# TelTail_Breakout_3v0.net
KiCad netlist of a schematic drawn in EAGLE
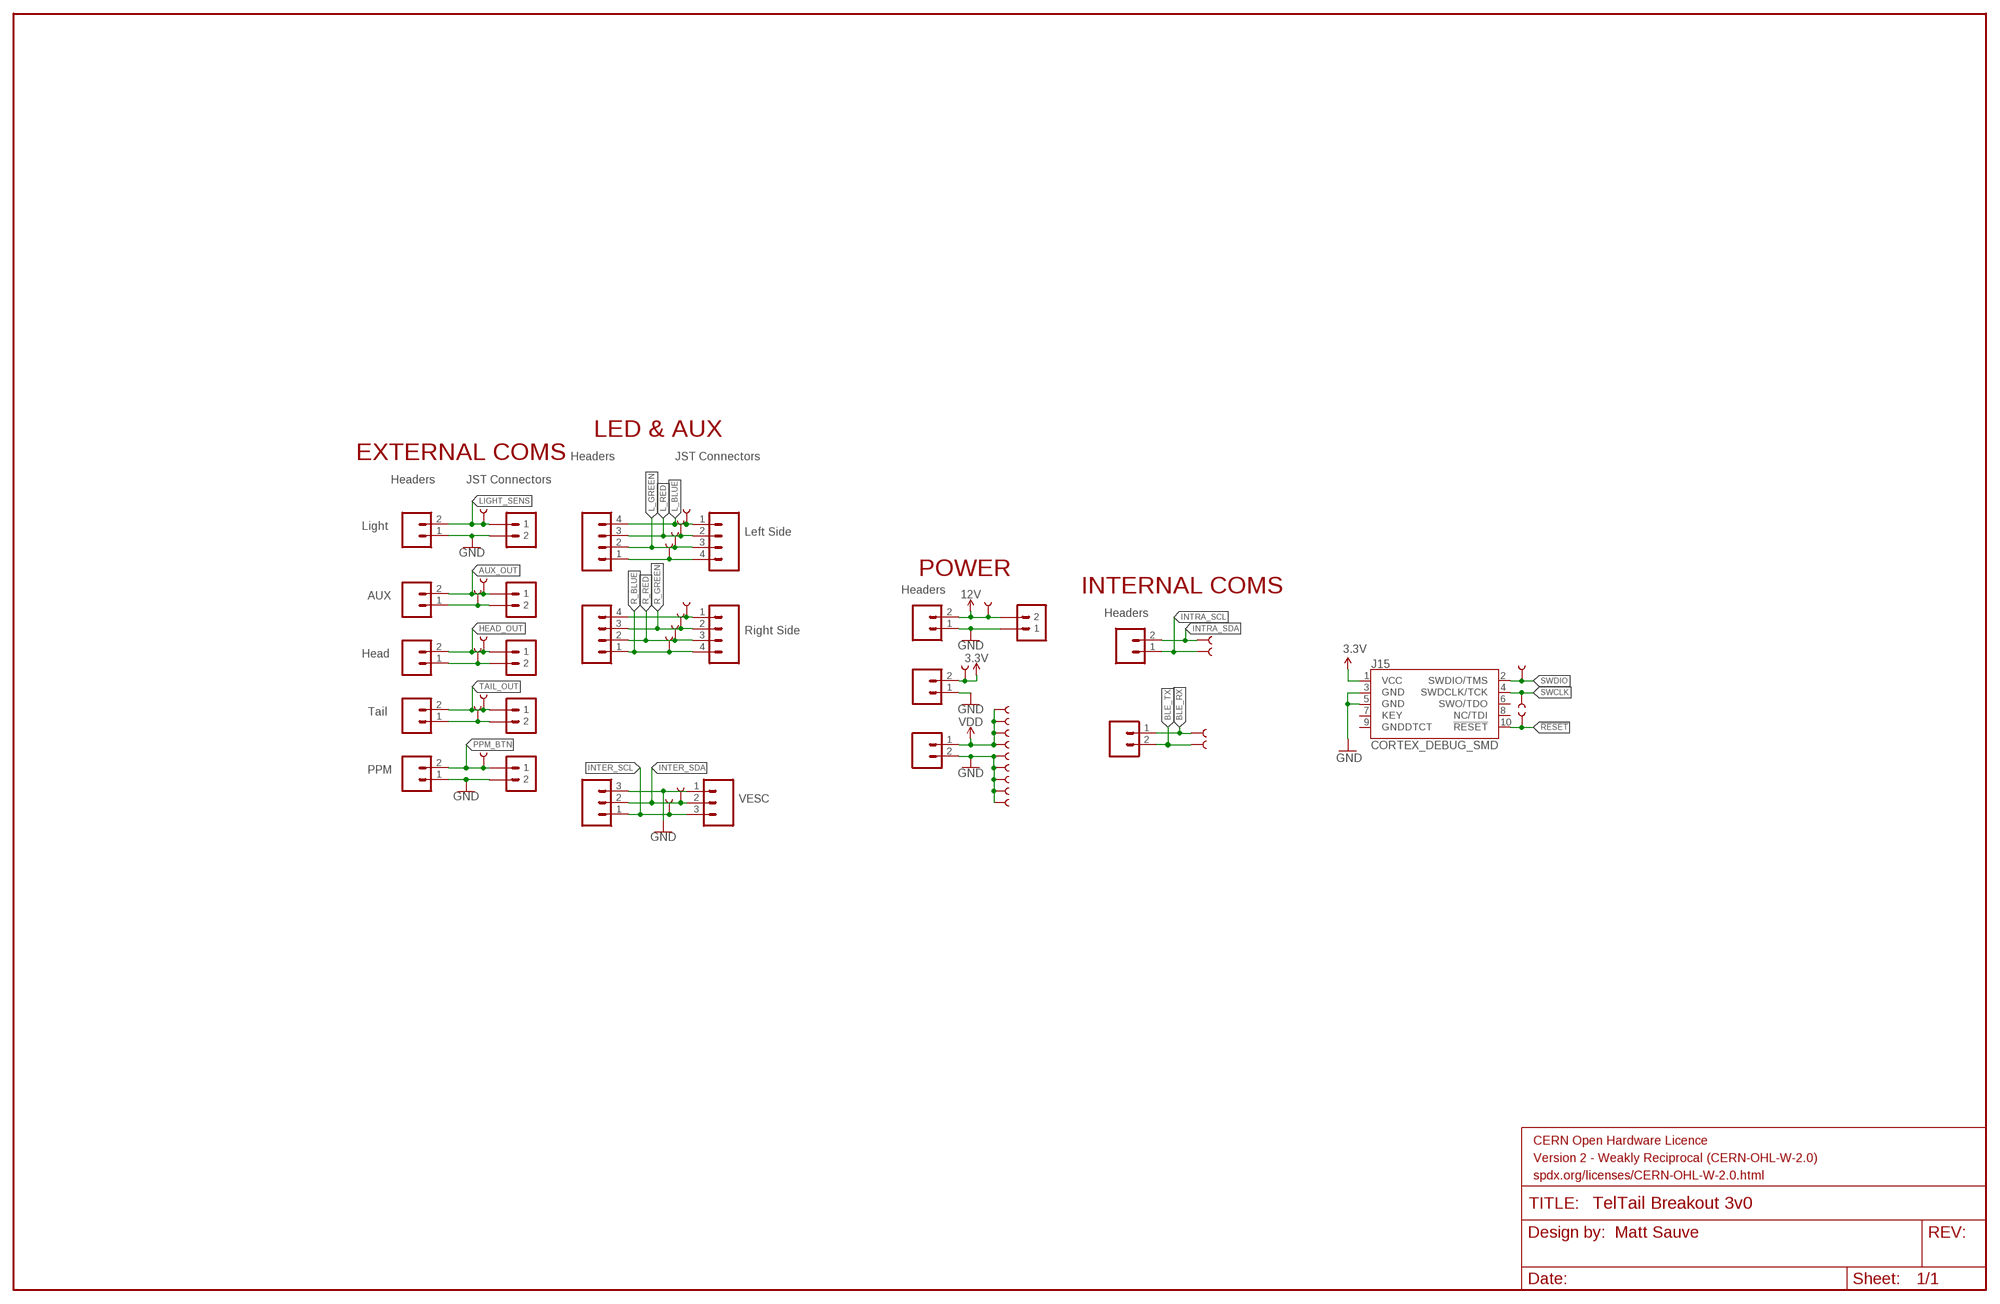
[diagram p0: schematic, sheet 1]

(export (version "E")
  (design (tool "Eeschema 10.0.6"))
  (components
    (comp (ref "FRAME1")
      (value "FRAME-LEDGER_CERN_WEAK")
      (footprint "eagle-import:CERN_WEAK")
      (libsource (lib "eagle-import") (part "FRAME-LEDGER_CERN_WEAK"))
    )
    (comp (ref "J1")
      (value "CONN_02")
      (footprint "eagle-import:1X02")
      (libsource (lib "eagle-import") (part "CONN_02"))
    )
    (comp (ref "J2")
      (value "CONN_02")
      (footprint "eagle-import:1X02")
      (libsource (lib "eagle-import") (part "CONN_02"))
    )
    (comp (ref "J3")
      (value "CONN_02")
      (footprint "eagle-import:1X02")
      (libsource (lib "eagle-import") (part "CONN_02"))
    )
    (comp (ref "J4")
      (value "CONN_02")
      (footprint "eagle-import:1X02")
      (libsource (lib "eagle-import") (part "CONN_02"))
    )
    (comp (ref "J5")
      (value "CONN_02")
      (footprint "eagle-import:1X02")
      (libsource (lib "eagle-import") (part "CONN_02"))
    )
    (comp (ref "J6")
      (value "CONN_02")
      (footprint "eagle-import:1X02")
      (libsource (lib "eagle-import") (part "CONN_02"))
    )
    (comp (ref "J7")
      (value "CONN_03")
      (footprint "eagle-import:1X03")
      (libsource (lib "eagle-import") (part "CONN_03"))
    )
    (comp (ref "J9")
      (value "CONN_04")
      (footprint "eagle-import:1X04")
      (libsource (lib "eagle-import") (part "CONN_04"))
    )
    (comp (ref "J10")
      (value "CONN_04")
      (footprint "eagle-import:1X04")
      (libsource (lib "eagle-import") (part "CONN_04"))
    )
    (comp (ref "J11")
      (value "CONN_02")
      (footprint "eagle-import:1X02")
      (libsource (lib "eagle-import") (part "CONN_02"))
    )
    (comp (ref "J12")
      (value "CONN_02")
      (footprint "eagle-import:1X02")
      (libsource (lib "eagle-import") (part "CONN_02"))
    )
    (comp (ref "J13")
      (value "CONN_02")
      (footprint "eagle-import:1X02")
      (libsource (lib "eagle-import") (part "CONN_02"))
    )
    (comp (ref "J14")
      (value "CONN_02")
      (footprint "eagle-import:1X02")
      (libsource (lib "eagle-import") (part "CONN_02"))
    )
    (comp (ref "J15")
      (value "CORTEX_DEBUG_SMD")
      (footprint "eagle-import:SAMTECH_FTSH-105-01")
      (libsource (lib "eagle-import") (part "CORTEX_DEBUG_SMD"))
    )
    (comp (ref "U$1")
      (value "JST_PH_2POS")
      (footprint "eagle-import:JST_PH_2POS")
      (libsource (lib "eagle-import") (part "JST_PH_2POS"))
    )
    (comp (ref "U$2")
      (value "JST_PH_2POS")
      (footprint "eagle-import:JST_PH_2POS")
      (libsource (lib "eagle-import") (part "JST_PH_2POS"))
    )
    (comp (ref "U$3")
      (value "JST_PH_2POS")
      (footprint "eagle-import:JST_PH_2POS")
      (libsource (lib "eagle-import") (part "JST_PH_2POS"))
    )
    (comp (ref "U$4")
      (value "JST_PH_2POS")
      (footprint "eagle-import:JST_PH_2POS")
      (libsource (lib "eagle-import") (part "JST_PH_2POS"))
    )
    (comp (ref "U$5")
      (value "JST_PH_2POS")
      (footprint "eagle-import:JST_PH_2POS")
      (libsource (lib "eagle-import") (part "JST_PH_2POS"))
    )
    (comp (ref "U$6")
      (value "POGO_PIN_90173-AS")
      (footprint "eagle-import:POGO_PIN_90173-AS")
      (libsource (lib "eagle-import") (part "POGO_PIN_90173-AS"))
    )
    (comp (ref "U$8")
      (value "JST_PH_4POS")
      (footprint "eagle-import:JST_PH_4POS")
      (libsource (lib "eagle-import") (part "JST_PH_4POS"))
    )
    (comp (ref "U$9")
      (value "JST_PH_3POS")
      (footprint "eagle-import:JST_PH_3POS")
      (libsource (lib "eagle-import") (part "JST_PH_3POS"))
    )
    (comp (ref "U$10")
      (value "JST_PH_4POS")
      (footprint "eagle-import:JST_PH_4POS")
      (libsource (lib "eagle-import") (part "JST_PH_4POS"))
    )
    (comp (ref "U$11")
      (value "POGO_PIN_90173-AS")
      (footprint "eagle-import:POGO_PIN_90173-AS")
      (libsource (lib "eagle-import") (part "POGO_PIN_90173-AS"))
    )
    (comp (ref "U$12")
      (value "POGO_PIN_90173-AS")
      (footprint "eagle-import:POGO_PIN_90173-AS")
      (libsource (lib "eagle-import") (part "POGO_PIN_90173-AS"))
    )
    (comp (ref "U$13")
      (value "POGO_PIN_90173-AS")
      (footprint "eagle-import:POGO_PIN_90173-AS")
      (libsource (lib "eagle-import") (part "POGO_PIN_90173-AS"))
    )
    (comp (ref "U$14")
      (value "POGO_PIN_90173-AS")
      (footprint "eagle-import:POGO_PIN_90173-AS")
      (libsource (lib "eagle-import") (part "POGO_PIN_90173-AS"))
    )
    (comp (ref "U$15")
      (value "POGO_PIN_90173-AS")
      (footprint "eagle-import:POGO_PIN_90173-AS")
      (libsource (lib "eagle-import") (part "POGO_PIN_90173-AS"))
    )
    (comp (ref "U$16")
      (value "POGO_PIN_90173-AS")
      (footprint "eagle-import:POGO_PIN_90173-AS")
      (libsource (lib "eagle-import") (part "POGO_PIN_90173-AS"))
    )
    (comp (ref "U$17")
      (value "POGO_PIN_90173-AS")
      (footprint "eagle-import:POGO_PIN_90173-AS")
      (libsource (lib "eagle-import") (part "POGO_PIN_90173-AS"))
    )
    (comp (ref "U$18")
      (value "POGO_PIN_90173-AS")
      (footprint "eagle-import:POGO_PIN_90173-AS")
      (libsource (lib "eagle-import") (part "POGO_PIN_90173-AS"))
    )
    (comp (ref "U$19")
      (value "POGO_PIN_90173-AS")
      (footprint "eagle-import:POGO_PIN_90173-AS")
      (libsource (lib "eagle-import") (part "POGO_PIN_90173-AS"))
    )
    (comp (ref "U$20")
      (value "POGO_PIN_90173-AS")
      (footprint "eagle-import:POGO_PIN_90173-AS")
      (libsource (lib "eagle-import") (part "POGO_PIN_90173-AS"))
    )
    (comp (ref "U$21")
      (value "POGO_PIN_90173-AS")
      (footprint "eagle-import:POGO_PIN_90173-AS")
      (libsource (lib "eagle-import") (part "POGO_PIN_90173-AS"))
    )
    (comp (ref "U$22")
      (value "POGO_PIN_90173-AS")
      (footprint "eagle-import:POGO_PIN_90173-AS")
      (libsource (lib "eagle-import") (part "POGO_PIN_90173-AS"))
    )
    (comp (ref "U$23")
      (value "POGO_PIN_90173-AS")
      (footprint "eagle-import:POGO_PIN_90173-AS")
      (libsource (lib "eagle-import") (part "POGO_PIN_90173-AS"))
    )
    (comp (ref "U$24")
      (value "POGO_PIN_90173-AS")
      (footprint "eagle-import:POGO_PIN_90173-AS")
      (libsource (lib "eagle-import") (part "POGO_PIN_90173-AS"))
    )
    (comp (ref "U$25")
      (value "POGO_PIN_90173-AS")
      (footprint "eagle-import:POGO_PIN_90173-AS")
      (libsource (lib "eagle-import") (part "POGO_PIN_90173-AS"))
    )
    (comp (ref "U$26")
      (value "POGO_PIN_90173-AS")
      (footprint "eagle-import:POGO_PIN_90173-AS")
      (libsource (lib "eagle-import") (part "POGO_PIN_90173-AS"))
    )
    (comp (ref "U$27")
      (value "POGO_PIN_90173-AS")
      (footprint "eagle-import:POGO_PIN_90173-AS")
      (libsource (lib "eagle-import") (part "POGO_PIN_90173-AS"))
    )
    (comp (ref "U$28")
      (value "POGO_PIN_90173-AS")
      (footprint "eagle-import:POGO_PIN_90173-AS")
      (libsource (lib "eagle-import") (part "POGO_PIN_90173-AS"))
    )
    (comp (ref "U$29")
      (value "POGO_PIN_90173-AS")
      (footprint "eagle-import:POGO_PIN_90173-AS")
      (libsource (lib "eagle-import") (part "POGO_PIN_90173-AS"))
    )
    (comp (ref "U$30")
      (value "POGO_PIN_90173-AS")
      (footprint "eagle-import:POGO_PIN_90173-AS")
      (libsource (lib "eagle-import") (part "POGO_PIN_90173-AS"))
    )
    (comp (ref "U$31")
      (value "POGO_PIN_90173-AS")
      (footprint "eagle-import:POGO_PIN_90173-AS")
      (libsource (lib "eagle-import") (part "POGO_PIN_90173-AS"))
    )
    (comp (ref "U$32")
      (value "POGO_PIN_90173-AS")
      (footprint "eagle-import:POGO_PIN_90173-AS")
      (libsource (lib "eagle-import") (part "POGO_PIN_90173-AS"))
    )
    (comp (ref "U$33")
      (value "POGO_PIN_90173-AS")
      (footprint "eagle-import:POGO_PIN_90173-AS")
      (libsource (lib "eagle-import") (part "POGO_PIN_90173-AS"))
    )
    (comp (ref "U$34")
      (value "POGO_PIN_90173-AS")
      (footprint "eagle-import:POGO_PIN_90173-AS")
      (libsource (lib "eagle-import") (part "POGO_PIN_90173-AS"))
    )
    (comp (ref "U$35")
      (value "POGO_PIN_90173-AS")
      (footprint "eagle-import:POGO_PIN_90173-AS")
      (libsource (lib "eagle-import") (part "POGO_PIN_90173-AS"))
    )
    (comp (ref "U$36")
      (value "POGO_PIN_90173-AS")
      (footprint "eagle-import:POGO_PIN_90173-AS")
      (libsource (lib "eagle-import") (part "POGO_PIN_90173-AS"))
    )
    (comp (ref "U$37")
      (value "POGO_PIN_90173-AS")
      (footprint "eagle-import:POGO_PIN_90173-AS")
      (libsource (lib "eagle-import") (part "POGO_PIN_90173-AS"))
    )
    (comp (ref "U$38")
      (value "POGO_PIN_90173-AS")
      (footprint "eagle-import:POGO_PIN_90173-AS")
      (libsource (lib "eagle-import") (part "POGO_PIN_90173-AS"))
    )
    (comp (ref "U$39")
      (value "POGO_PIN_90173-AS")
      (footprint "eagle-import:POGO_PIN_90173-AS")
      (libsource (lib "eagle-import") (part "POGO_PIN_90173-AS"))
    )
    (comp (ref "U$40")
      (value "POGO_PIN_90173-AS")
      (footprint "eagle-import:POGO_PIN_90173-AS")
      (libsource (lib "eagle-import") (part "POGO_PIN_90173-AS"))
    )
    (comp (ref "U$42")
      (value "POGO_PIN_90173-AS")
      (footprint "eagle-import:POGO_PIN_90173-AS")
      (libsource (lib "eagle-import") (part "POGO_PIN_90173-AS"))
    )
    (comp (ref "U$43")
      (value "POGO_PIN_90173-AS")
      (footprint "eagle-import:POGO_PIN_90173-AS")
      (libsource (lib "eagle-import") (part "POGO_PIN_90173-AS"))
    )
    (comp (ref "U$44")
      (value "POGO_PIN_90173-AS")
      (footprint "eagle-import:POGO_PIN_90173-AS")
      (libsource (lib "eagle-import") (part "POGO_PIN_90173-AS"))
    )
    (comp (ref "U$45")
      (value "JST_PH_2POS")
      (footprint "eagle-import:JST_PH_2POS")
      (libsource (lib "eagle-import") (part "JST_PH_2POS"))
    )
    (comp (ref "U$46")
      (value "POGO_PIN_90173-AS")
      (footprint "eagle-import:POGO_PIN_90173-AS")
      (libsource (lib "eagle-import") (part "POGO_PIN_90173-AS"))
    )
    (comp (ref "U$48")
      (value "POGO_PIN_90173-AS")
      (footprint "eagle-import:POGO_PIN_90173-AS")
      (libsource (lib "eagle-import") (part "POGO_PIN_90173-AS"))
    )
  )
  (nets
    (net (code "1") (name "/~{RESET}") (class "Default")
      (node (ref "J15") (pin "10") (pinfunction "~{RESET}_10") (pintype "bidirectional"))
      (node (ref "U$36") (pin "P$1") (pinfunction "1_P$1") (pintype "bidirectional"))
    )
    (net (code "2") (name "3.3V") (class "Default")
      (node (ref "J12") (pin "2") (pinfunction "2_2") (pintype "passive"))
      (node (ref "J15") (pin "1") (pinfunction "VCC_1") (pintype "bidirectional"))
      (node (ref "U$20") (pin "P$1") (pinfunction "1_P$1") (pintype "bidirectional"))
    )
    (net (code "3") (name "12V") (class "Default")
      (node (ref "J11") (pin "2") (pinfunction "2_2") (pintype "passive"))
      (node (ref "U$38") (pin "P$1") (pinfunction "1_P$1") (pintype "bidirectional"))
      (node (ref "U$45") (pin "2") (pinfunction "2_2") (pintype "passive"))
    )
    (net (code "4") (name "AUX_OUT") (class "Default")
      (node (ref "J2") (pin "2") (pinfunction "2_2") (pintype "passive"))
      (node (ref "U$31") (pin "P$1") (pinfunction "1_P$1") (pintype "bidirectional"))
      (node (ref "U$4") (pin "1") (pinfunction "1_1") (pintype "passive"))
    )
    (net (code "5") (name "BLE_RX") (class "Default")
      (node (ref "J14") (pin "1") (pinfunction "1_1") (pintype "passive"))
      (node (ref "U$46") (pin "P$1") (pinfunction "1_P$1") (pintype "bidirectional"))
    )
    (net (code "6") (name "BLE_TX") (class "Default")
      (node (ref "J14") (pin "2") (pinfunction "2_2") (pintype "passive"))
      (node (ref "U$48") (pin "P$1") (pinfunction "1_P$1") (pintype "bidirectional"))
    )
    (net (code "7") (name "GND") (class "Default")
      (node (ref "J1") (pin "1") (pinfunction "1_1") (pintype "passive"))
      (node (ref "J11") (pin "1") (pinfunction "1_1") (pintype "passive"))
      (node (ref "J12") (pin "1") (pinfunction "1_1") (pintype "passive"))
      (node (ref "J15") (pin "3") (pinfunction "GND_3") (pintype "bidirectional"))
      (node (ref "J15") (pin "5") (pinfunction "GND_5") (pintype "bidirectional"))
      (node (ref "J5") (pin "1") (pinfunction "1_1") (pintype "passive"))
      (node (ref "J6") (pin "2") (pinfunction "2_2") (pintype "passive"))
      (node (ref "J7") (pin "3") (pinfunction "3_3") (pintype "passive"))
      (node (ref "U$1") (pin "2") (pinfunction "2_2") (pintype "passive"))
      (node (ref "U$24") (pin "P$1") (pinfunction "1_P$1") (pintype "bidirectional"))
      (node (ref "U$28") (pin "P$1") (pinfunction "1_P$1") (pintype "bidirectional"))
      (node (ref "U$30") (pin "P$1") (pinfunction "1_P$1") (pintype "bidirectional"))
      (node (ref "U$40") (pin "P$1") (pinfunction "1_P$1") (pintype "bidirectional"))
      (node (ref "U$45") (pin "1") (pinfunction "1_1") (pintype "passive"))
      (node (ref "U$5") (pin "2") (pinfunction "2_2") (pintype "passive"))
      (node (ref "U$6") (pin "P$1") (pinfunction "1_P$1") (pintype "bidirectional"))
      (node (ref "U$9") (pin "1") (pinfunction "2_1") (pintype "passive"))
    )
    (net (code "8") (name "HEAD_OUT") (class "Default")
      (node (ref "J3") (pin "2") (pinfunction "2_2") (pintype "passive"))
      (node (ref "U$29") (pin "P$1") (pinfunction "1_P$1") (pintype "bidirectional"))
      (node (ref "U$3") (pin "1") (pinfunction "1_1") (pintype "passive"))
    )
    (net (code "9") (name "INTER_SCL") (class "Default")
      (node (ref "J7") (pin "1") (pinfunction "1_1") (pintype "passive"))
      (node (ref "U$19") (pin "P$1") (pinfunction "1_P$1") (pintype "bidirectional"))
      (node (ref "U$9") (pin "3") (pinfunction "4_3") (pintype "passive"))
    )
    (net (code "10") (name "INTER_SDA") (class "Default")
      (node (ref "J7") (pin "2") (pinfunction "2_2") (pintype "passive"))
      (node (ref "U$21") (pin "P$1") (pinfunction "1_P$1") (pintype "bidirectional"))
      (node (ref "U$9") (pin "2") (pinfunction "3_2") (pintype "passive"))
    )
    (net (code "11") (name "INTRA_SCL") (class "Default")
      (node (ref "J13") (pin "1") (pinfunction "1_1") (pintype "passive"))
      (node (ref "U$44") (pin "P$1") (pinfunction "1_P$1") (pintype "bidirectional"))
    )
    (net (code "12") (name "INTRA_SDA") (class "Default")
      (node (ref "J13") (pin "2") (pinfunction "2_2") (pintype "passive"))
      (node (ref "U$43") (pin "P$1") (pinfunction "1_P$1") (pintype "bidirectional"))
    )
    (net (code "13") (name "LIGHT_SENS") (class "Default")
      (node (ref "J1") (pin "2") (pinfunction "2_2") (pintype "passive"))
      (node (ref "U$33") (pin "P$1") (pinfunction "1_P$1") (pintype "bidirectional"))
      (node (ref "U$5") (pin "1") (pinfunction "1_1") (pintype "passive"))
    )
    (net (code "14") (name "L_BLUE") (class "Default")
      (node (ref "J10") (pin "4") (pinfunction "4_4") (pintype "passive"))
      (node (ref "U$10") (pin "1") (pinfunction "1_1") (pintype "passive"))
      (node (ref "U$11") (pin "P$1") (pinfunction "1_P$1") (pintype "bidirectional"))
    )
    (net (code "15") (name "L_GREEN") (class "Default")
      (node (ref "J10") (pin "2") (pinfunction "2_2") (pintype "passive"))
      (node (ref "U$10") (pin "3") (pinfunction "3_3") (pintype "passive"))
      (node (ref "U$13") (pin "P$1") (pinfunction "1_P$1") (pintype "bidirectional"))
    )
    (net (code "16") (name "L_RED") (class "Default")
      (node (ref "J10") (pin "3") (pinfunction "3_3") (pintype "passive"))
      (node (ref "U$10") (pin "2") (pinfunction "2_2") (pintype "passive"))
      (node (ref "U$12") (pin "P$1") (pinfunction "1_P$1") (pintype "bidirectional"))
    )
    (net (code "17") (name "Net-(U$14-1)") (class "Default")
      (node (ref "J10") (pin "1") (pinfunction "1_1") (pintype "passive"))
      (node (ref "U$10") (pin "4") (pinfunction "4_4") (pintype "passive"))
      (node (ref "U$14") (pin "P$1") (pinfunction "1_P$1") (pintype "bidirectional"))
    )
    (net (code "18") (name "Net-(U$15-1)") (class "Default")
      (node (ref "J9") (pin "4") (pinfunction "4_4") (pintype "passive"))
      (node (ref "U$15") (pin "P$1") (pinfunction "1_P$1") (pintype "bidirectional"))
      (node (ref "U$8") (pin "1") (pinfunction "1_1") (pintype "passive"))
    )
    (net (code "19") (name "Net-(U$32-1)") (class "Default")
      (node (ref "J2") (pin "1") (pinfunction "1_1") (pintype "passive"))
      (node (ref "U$32") (pin "P$1") (pinfunction "1_P$1") (pintype "bidirectional"))
      (node (ref "U$4") (pin "2") (pinfunction "2_2") (pintype "passive"))
    )
    (net (code "20") (name "Net-(U$34-1)") (class "Default")
      (node (ref "J3") (pin "1") (pinfunction "1_1") (pintype "passive"))
      (node (ref "U$3") (pin "2") (pinfunction "2_2") (pintype "passive"))
      (node (ref "U$34") (pin "P$1") (pinfunction "1_P$1") (pintype "bidirectional"))
    )
    (net (code "21") (name "Net-(U$35-1)") (class "Default")
      (node (ref "J4") (pin "1") (pinfunction "1_1") (pintype "passive"))
      (node (ref "U$2") (pin "2") (pinfunction "2_2") (pintype "passive"))
      (node (ref "U$35") (pin "P$1") (pinfunction "1_P$1") (pintype "bidirectional"))
    )
    (net (code "22") (name "PPM_BTN") (class "Default")
      (node (ref "J5") (pin "2") (pinfunction "2_2") (pintype "passive"))
      (node (ref "U$1") (pin "1") (pinfunction "1_1") (pintype "passive"))
      (node (ref "U$25") (pin "P$1") (pinfunction "1_P$1") (pintype "bidirectional"))
    )
    (net (code "23") (name "R_BLUE") (class "Default")
      (node (ref "J9") (pin "1") (pinfunction "1_1") (pintype "passive"))
      (node (ref "U$18") (pin "P$1") (pinfunction "1_P$1") (pintype "bidirectional"))
      (node (ref "U$8") (pin "4") (pinfunction "4_4") (pintype "passive"))
    )
    (net (code "24") (name "R_GREEN") (class "Default")
      (node (ref "J9") (pin "3") (pinfunction "3_3") (pintype "passive"))
      (node (ref "U$16") (pin "P$1") (pinfunction "1_P$1") (pintype "bidirectional"))
      (node (ref "U$8") (pin "2") (pinfunction "2_2") (pintype "passive"))
    )
    (net (code "25") (name "R_RED") (class "Default")
      (node (ref "J9") (pin "2") (pinfunction "2_2") (pintype "passive"))
      (node (ref "U$17") (pin "P$1") (pinfunction "1_P$1") (pintype "bidirectional"))
      (node (ref "U$8") (pin "3") (pinfunction "3_3") (pintype "passive"))
    )
    (net (code "26") (name "SWCLK") (class "Default")
      (node (ref "J15") (pin "4") (pinfunction "SWDCLK/TCK_4") (pintype "bidirectional"))
      (node (ref "U$37") (pin "P$1") (pinfunction "1_P$1") (pintype "bidirectional"))
    )
    (net (code "27") (name "SWDIO") (class "Default")
      (node (ref "J15") (pin "2") (pinfunction "SWDIO/TMS_2") (pintype "bidirectional"))
      (node (ref "U$39") (pin "P$1") (pinfunction "1_P$1") (pintype "bidirectional"))
    )
    (net (code "28") (name "TAIL_OUT") (class "Default")
      (node (ref "J4") (pin "2") (pinfunction "2_2") (pintype "passive"))
      (node (ref "U$2") (pin "1") (pinfunction "1_1") (pintype "passive"))
      (node (ref "U$27") (pin "P$1") (pinfunction "1_P$1") (pintype "bidirectional"))
    )
    (net (code "29") (name "VDD") (class "Default")
      (node (ref "J6") (pin "1") (pinfunction "1_1") (pintype "passive"))
      (node (ref "U$22") (pin "P$1") (pinfunction "1_P$1") (pintype "bidirectional"))
      (node (ref "U$23") (pin "P$1") (pinfunction "1_P$1") (pintype "bidirectional"))
      (node (ref "U$26") (pin "P$1") (pinfunction "1_P$1") (pintype "bidirectional"))
      (node (ref "U$42") (pin "P$1") (pinfunction "1_P$1") (pintype "bidirectional"))
    )
    (net (code "30") (name "unconnected-(J15-GNDDTCT-Pad9)") (class "Default")
      (node (ref "J15") (pin "9") (pinfunction "GNDDTCT_9") (pintype "bidirectional"))
    )
    (net (code "31") (name "unconnected-(J15-KEY-Pad7)") (class "Default")
      (node (ref "J15") (pin "7") (pinfunction "KEY_7") (pintype "bidirectional"))
    )
    (net (code "32") (name "unconnected-(J15-NC{slash}TDI-Pad8)") (class "Default")
      (node (ref "J15") (pin "8") (pinfunction "NC/TDI_8") (pintype "bidirectional"))
    )
    (net (code "33") (name "unconnected-(J15-SWO{slash}TDO-Pad6)") (class "Default")
      (node (ref "J15") (pin "6") (pinfunction "SWO/TDO_6") (pintype "bidirectional"))
    )
  )
)
